# AmplifierOutput.net
KiCad netlist of a schematic drawn in Altium Designer
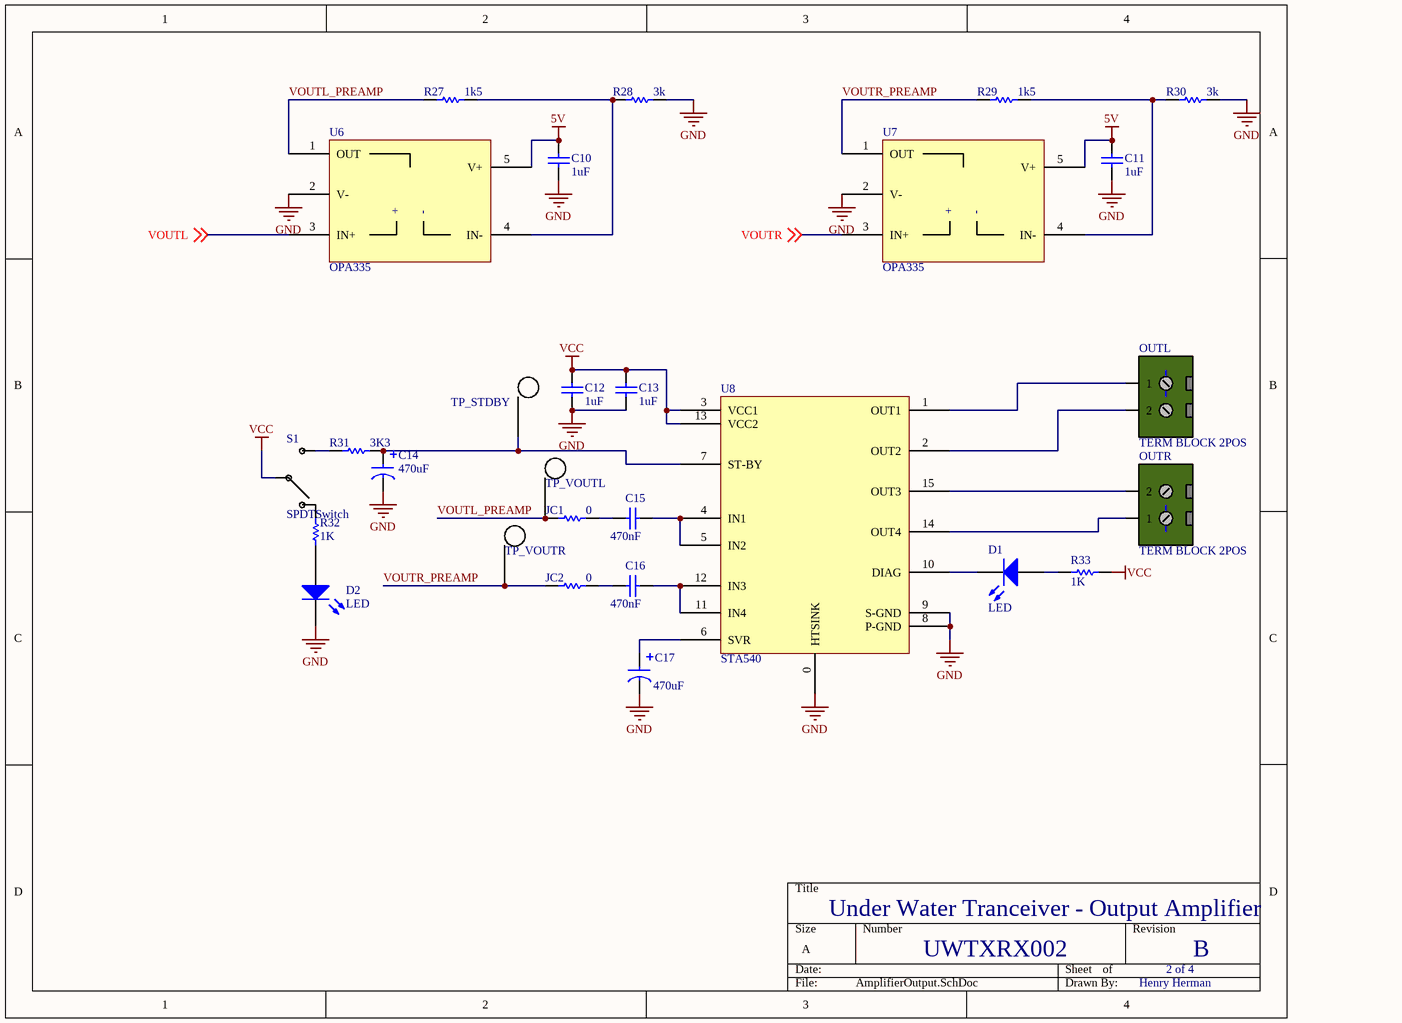
[diagram p0: AmplifierOutput.SchDoc]

(export (version "E")
  (design (tool "Eeschema 10.0.6"))
  (components
    (comp (ref "C10")
      (value "1uF")
      (footprint "SM/C_0805")
      (description "CAP")
      (libsource (lib "Henry1_20_2010") (part "CAP"))
    )
    (comp (ref "C11")
      (value "1uF")
      (footprint "SM/C_0805")
      (description "CAP")
      (libsource (lib "Henry1_20_2010") (part "CAP"))
    )
    (comp (ref "C12")
      (value "1uF")
      (footprint "SM/C_0805")
      (description "CAP")
      (libsource (lib "Henry1_20_2010") (part "CAP"))
    )
    (comp (ref "C13")
      (value "1uF")
      (footprint "SM/C_0805")
      (description "CAP")
      (libsource (lib "Henry1_20_2010") (part "CAP"))
    )
    (comp (ref "C14")
      (value "470uF")
      (footprint "SM/CT_6032_12")
      (description "CAP")
      (fields (field (name "Comment") "CAP_POL"))
      (libsource (lib "Henry1_20_2010") (part "CAP_POL"))
    )
    (comp (ref "C15")
      (value "470nF")
      (footprint "SM/C_0805")
      (description "CAP")
      (libsource (lib "Henry1_20_2010") (part "CAP"))
    )
    (comp (ref "C16")
      (value "470nF")
      (footprint "SM/C_0805")
      (description "CAP")
      (libsource (lib "Henry1_20_2010") (part "CAP"))
    )
    (comp (ref "C17")
      (value "470uF")
      (footprint "SM/CT_6032_12")
      (description "CAP")
      (fields (field (name "Comment") "CAP_POL"))
      (libsource (lib "Henry1_20_2010") (part "CAP_POL"))
    )
    (comp (ref "D1") (value "LED") (footprint "LED-0805") (libsource (lib "Henry1_20_2010") (part "LED")))
    (comp (ref "D2") (value "LED") (footprint "LED-0805") (libsource (lib "Henry1_20_2010") (part "LED")))
    (comp (ref "JC1")
      (value "0")
      (footprint "SM/R_0805")
      (description "Resistor")
      (fields (field (name "Comment") "Res") (field (name "PUBLISHER") "Altium Limited"))
      (libsource (lib "Henry1_20_2010") (part "Res"))
    )
    (comp (ref "JC2")
      (value "0")
      (footprint "SM/R_0805")
      (description "Resistor")
      (fields (field (name "Comment") "Res") (field (name "PUBLISHER") "Altium Limited"))
      (libsource (lib "Henry1_20_2010") (part "Res"))
    )
    (comp (ref "OUTL")
      (value "TERM BLOCK 2POS")
      (footprint "Conn-ScrewTerminal-2pin-Phoenix")
      (libsource (lib "Henry1_20_2010") (part "2Pin-PhoenixTerminalBlock"))
    )
    (comp (ref "OUTR")
      (value "TERM BLOCK 2POS")
      (footprint "Conn-ScrewTerminal-2pin-Phoenix")
      (libsource (lib "") (part "2Pin-PhoenixTerminalBlock_1"))
    )
    (comp (ref "R27")
      (value "1k5")
      (footprint "SM/R_0805")
      (description "Resistor")
      (fields (field (name "Comment") "Res") (field (name "PUBLISHER") "Altium Limited"))
      (libsource (lib "Henry1_20_2010") (part "Res"))
    )
    (comp (ref "R28")
      (value "3k")
      (footprint "SM/R_0805")
      (description "Resistor")
      (fields (field (name "Comment") "Res") (field (name "PUBLISHER") "Altium Limited"))
      (libsource (lib "Henry1_20_2010") (part "Res"))
    )
    (comp (ref "R29")
      (value "1k5")
      (footprint "SM/R_0805")
      (description "Resistor")
      (fields (field (name "Comment") "Res") (field (name "PUBLISHER") "Altium Limited"))
      (libsource (lib "Henry1_20_2010") (part "Res"))
    )
    (comp (ref "R30")
      (value "3k")
      (footprint "SM/R_0805")
      (description "Resistor")
      (fields (field (name "Comment") "Res") (field (name "PUBLISHER") "Altium Limited"))
      (libsource (lib "Henry1_20_2010") (part "Res"))
    )
    (comp (ref "R31")
      (value "3K3")
      (footprint "SM/R_0805")
      (description "Resistor")
      (fields (field (name "Comment") "Res") (field (name "PUBLISHER") "Altium Limited"))
      (libsource (lib "Henry1_20_2010") (part "Res"))
    )
    (comp (ref "R32")
      (value "1K")
      (footprint "SM/R_0805")
      (description "Resistor")
      (fields (field (name "Comment") "Res") (field (name "PUBLISHER") "Altium Limited"))
      (libsource (lib "Henry1_20_2010") (part "Res"))
    )
    (comp (ref "R33")
      (value "1K")
      (footprint "SM/R_0805")
      (description "Resistor")
      (fields (field (name "Comment") "Res") (field (name "PUBLISHER") "Altium Limited"))
      (libsource (lib "Henry1_20_2010") (part "Res"))
    )
    (comp (ref "S1")
      (value "SPDTSwitch")
      (footprint "SPDTSwitch")
      (libsource (lib "Henry1_20_2010") (part "SPDTSwitch"))
    )
    (comp (ref "TP_STDBY")
      (value "TEST_PT")
      (footprint "TEST_PT_SMD")
      (libsource (lib "Henry1_20_2010") (part "TEST_PT"))
    )
    (comp (ref "TP_VOUTL")
      (value "TEST_PT")
      (footprint "TEST_PT_SMD")
      (libsource (lib "Henry1_20_2010") (part "TEST_PT"))
    )
    (comp (ref "TP_VOUTR")
      (value "TEST_PT")
      (footprint "TEST_PT_SMD")
      (libsource (lib "Henry1_20_2010") (part "TEST_PT"))
    )
    (comp (ref "U6")
      (value "OPA335")
      (footprint "SOT23-5 -TI")
      (libsource (lib "Henry1_20_2010") (part "OPA335"))
    )
    (comp (ref "U7")
      (value "OPA335")
      (footprint "SOT23-5 -TI")
      (libsource (lib "Henry1_20_2010") (part "OPA335"))
    )
    (comp (ref "U8")
      (value "STA540")
      (footprint "STA540_Multiwatt15")
      (libsource (lib "Henry1_20_2010") (part "STA540"))
    )
  )
  (nets
    (net (code "1") (name "/VOUTL_PREAMP") (class "Default")
      (node (ref "JC1") (pin "1") (pinfunction "1_1") (pintype "passive"))
      (node (ref "R27") (pin "1") (pinfunction "1_1") (pintype "passive"))
      (node (ref "TP_VOUTL") (pin "1") (pinfunction "TP?_1") (pintype "passive"))
      (node (ref "U6") (pin "1") (pinfunction "OUT_1") (pintype "passive"))
    )
    (net (code "2") (name "/VOUTR_PREAMP") (class "Default")
      (node (ref "JC2") (pin "1") (pinfunction "1_1") (pintype "passive"))
      (node (ref "R29") (pin "1") (pinfunction "1_1") (pintype "passive"))
      (node (ref "TP_VOUTR") (pin "1") (pinfunction "TP?_1") (pintype "passive"))
      (node (ref "U7") (pin "1") (pinfunction "OUT_1") (pintype "passive"))
    )
    (net (code "3") (name "5V") (class "Default")
      (node (ref "C10") (pin "1") (pinfunction "1_1") (pintype "passive"))
      (node (ref "C11") (pin "1") (pinfunction "1_1") (pintype "passive"))
      (node (ref "U6") (pin "5") (pinfunction "V+_5") (pintype "passive"))
      (node (ref "U7") (pin "5") (pinfunction "V+_5") (pintype "passive"))
    )
    (net (code "4") (name "GND") (class "Default")
      (node (ref "C10") (pin "2") (pinfunction "2_2") (pintype "passive"))
      (node (ref "C11") (pin "2") (pinfunction "2_2") (pintype "passive"))
      (node (ref "C12") (pin "1") (pinfunction "1_1") (pintype "passive"))
      (node (ref "C13") (pin "1") (pinfunction "1_1") (pintype "passive"))
      (node (ref "C14") (pin "2") (pinfunction "2_2") (pintype "passive"))
      (node (ref "C17") (pin "2") (pinfunction "2_2") (pintype "passive"))
      (node (ref "D2") (pin "2") (pinfunction "K_2") (pintype "passive"))
      (node (ref "R28") (pin "2") (pinfunction "2_2") (pintype "passive"))
      (node (ref "R30") (pin "2") (pinfunction "2_2") (pintype "passive"))
      (node (ref "U6") (pin "2") (pinfunction "V-_2") (pintype "passive"))
      (node (ref "U7") (pin "2") (pinfunction "V-_2") (pintype "passive"))
      (node (ref "U8") (pin "0") (pinfunction "HTSINK_0") (pintype "passive"))
      (node (ref "U8") (pin "8") (pinfunction "P-GND_8") (pintype "passive"))
      (node (ref "U8") (pin "9") (pinfunction "S-GND_9") (pintype "passive"))
    )
    (net (code "5") (name "Net-(C15-Pad1)") (class "Default")
      (node (ref "C15") (pin "1") (pinfunction "1_1") (pintype "passive"))
      (node (ref "JC1") (pin "2") (pinfunction "2_2") (pintype "passive"))
    )
    (net (code "6") (name "Net-(C16-Pad1)") (class "Default")
      (node (ref "C16") (pin "1") (pinfunction "1_1") (pintype "passive"))
      (node (ref "JC2") (pin "2") (pinfunction "2_2") (pintype "passive"))
    )
    (net (code "7") (name "Net-(D1-A)") (class "Default")
      (node (ref "D1") (pin "1") (pinfunction "A_1") (pintype "passive"))
      (node (ref "R33") (pin "2") (pinfunction "2_2") (pintype "passive"))
    )
    (net (code "8") (name "Net-(D1-K)") (class "Default")
      (node (ref "D1") (pin "2") (pinfunction "K_2") (pintype "passive"))
      (node (ref "U8") (pin "10") (pinfunction "DIAG_10") (pintype "passive"))
    )
    (net (code "9") (name "Net-(D2-A)") (class "Default")
      (node (ref "D2") (pin "1") (pinfunction "A_1") (pintype "passive"))
      (node (ref "R32") (pin "2") (pinfunction "2_2") (pintype "passive"))
    )
    (net (code "10") (name "Net-(S1-P1)") (class "Default")
      (node (ref "R32") (pin "1") (pinfunction "1_1") (pintype "passive"))
      (node (ref "S1") (pin "1") (pinfunction "P1_1") (pintype "passive"))
    )
    (net (code "11") (name "Net-(S1-P2)") (class "Default")
      (node (ref "R31") (pin "1") (pinfunction "1_1") (pintype "passive"))
      (node (ref "S1") (pin "3") (pinfunction "P2_3") (pintype "passive"))
    )
    (net (code "12") (name "Net-(TP_STDBY-TP?)") (class "Default")
      (node (ref "C14") (pin "1") (pinfunction "1_1") (pintype "passive"))
      (node (ref "R31") (pin "2") (pinfunction "2_2") (pintype "passive"))
      (node (ref "TP_STDBY") (pin "1") (pinfunction "TP?_1") (pintype "passive"))
      (node (ref "U8") (pin "7") (pinfunction "ST-BY_7") (pintype "passive"))
    )
    (net (code "13") (name "Net-(U6-IN-)") (class "Default")
      (node (ref "R27") (pin "2") (pinfunction "2_2") (pintype "passive"))
      (node (ref "R28") (pin "1") (pinfunction "1_1") (pintype "passive"))
      (node (ref "U6") (pin "4") (pinfunction "IN-_4") (pintype "passive"))
    )
    (net (code "14") (name "Net-(U7-IN-)") (class "Default")
      (node (ref "R29") (pin "2") (pinfunction "2_2") (pintype "passive"))
      (node (ref "R30") (pin "1") (pinfunction "1_1") (pintype "passive"))
      (node (ref "U7") (pin "4") (pinfunction "IN-_4") (pintype "passive"))
    )
    (net (code "15") (name "Net-(U8-IN1)") (class "Default")
      (node (ref "C15") (pin "2") (pinfunction "2_2") (pintype "passive"))
      (node (ref "U8") (pin "4") (pinfunction "IN1_4") (pintype "passive"))
      (node (ref "U8") (pin "5") (pinfunction "IN2_5") (pintype "passive"))
    )
    (net (code "16") (name "Net-(U8-IN3)") (class "Default")
      (node (ref "C16") (pin "2") (pinfunction "2_2") (pintype "passive"))
      (node (ref "U8") (pin "11") (pinfunction "IN4_11") (pintype "passive"))
      (node (ref "U8") (pin "12") (pinfunction "IN3_12") (pintype "passive"))
    )
    (net (code "17") (name "Net-(U8-OUT1)") (class "Default")
      (node (ref "OUTL") (pin "1") (pinfunction "1_1") (pintype "passive"))
      (node (ref "U8") (pin "1") (pinfunction "OUT1_1") (pintype "passive"))
    )
    (net (code "18") (name "Net-(U8-OUT2)") (class "Default")
      (node (ref "OUTL") (pin "2") (pinfunction "2_2") (pintype "passive"))
      (node (ref "U8") (pin "2") (pinfunction "OUT2_2") (pintype "passive"))
    )
    (net (code "19") (name "Net-(U8-OUT3)") (class "Default")
      (node (ref "OUTR") (pin "2") (pinfunction "2_2") (pintype "passive"))
      (node (ref "U8") (pin "15") (pinfunction "OUT3_15") (pintype "passive"))
    )
    (net (code "20") (name "Net-(U8-OUT4)") (class "Default")
      (node (ref "OUTR") (pin "1") (pinfunction "1_1") (pintype "passive"))
      (node (ref "U8") (pin "14") (pinfunction "OUT4_14") (pintype "passive"))
    )
    (net (code "21") (name "Net-(U8-SVR)") (class "Default")
      (node (ref "C17") (pin "1") (pinfunction "1_1") (pintype "passive"))
      (node (ref "U8") (pin "6") (pinfunction "SVR_6") (pintype "passive"))
    )
    (net (code "22") (name "VCC") (class "Default")
      (node (ref "C12") (pin "2") (pinfunction "2_2") (pintype "passive"))
      (node (ref "C13") (pin "2") (pinfunction "2_2") (pintype "passive"))
      (node (ref "R33") (pin "1") (pinfunction "1_1") (pintype "passive"))
      (node (ref "S1") (pin "2") (pinfunction "C_2") (pintype "passive"))
      (node (ref "U8") (pin "13") (pinfunction "VCC2_13") (pintype "passive"))
      (node (ref "U8") (pin "3") (pinfunction "VCC1_3") (pintype "passive"))
    )
    (net (code "23") (name "VOUTL") (class "Default")
      (node (ref "U6") (pin "3") (pinfunction "IN+_3") (pintype "passive"))
    )
    (net (code "24") (name "VOUTR") (class "Default")
      (node (ref "U7") (pin "3") (pinfunction "IN+_3") (pintype "passive"))
    )
  )
)
